# 328schema.net
KiCad netlist of a schematic drawn in EAGLE
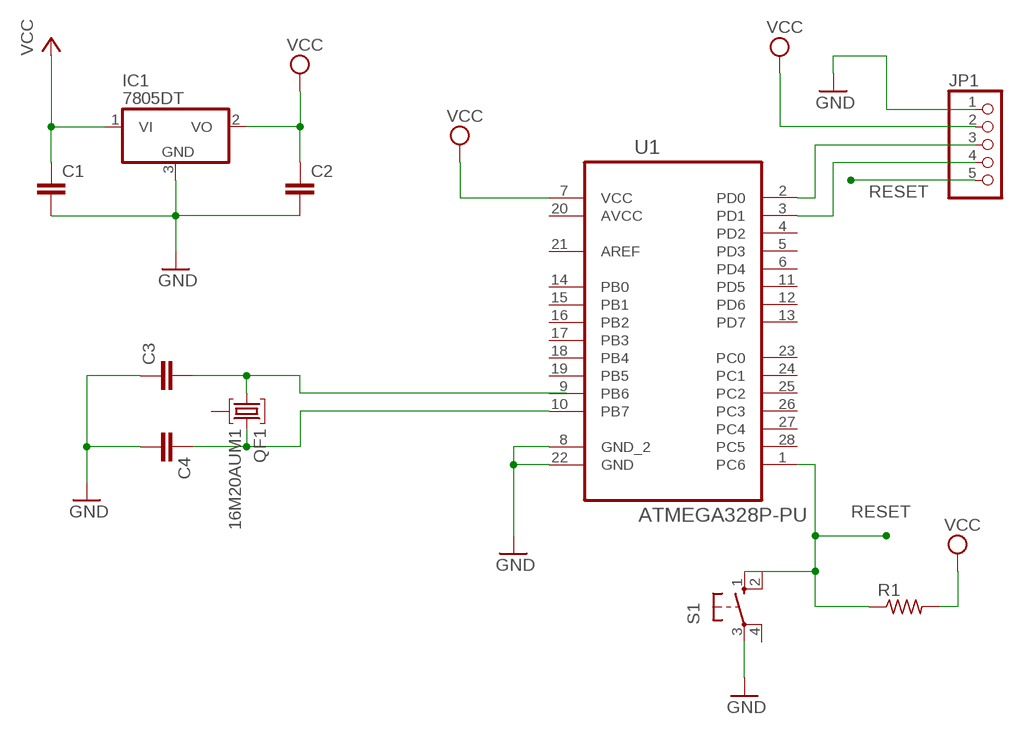
[diagram p0: schematic, sheet 1]

(export (version "E")
  (design (tool "Eeschema 10.0.6"))
  (components
    (comp (ref "C1")
      (value "C-EU025-025X050")
      (footprint "eagle-import:C025-025X050")
      (libsource (lib "eagle-import") (part "C-EU025-025X050"))
    )
    (comp (ref "C2")
      (value "C-EU025-025X050")
      (footprint "eagle-import:C025-025X050")
      (libsource (lib "eagle-import") (part "C-EU025-025X050"))
    )
    (comp (ref "C3")
      (value "C-EU025-025X050")
      (footprint "eagle-import:C025-025X050")
      (libsource (lib "eagle-import") (part "C-EU025-025X050"))
    )
    (comp (ref "C4")
      (value "C-EU025-025X050")
      (footprint "eagle-import:C025-025X050")
      (libsource (lib "eagle-import") (part "C-EU025-025X050"))
    )
    (comp (ref "IC1")
      (value "7805DT")
      (footprint "eagle-import:TO252")
      (libsource (lib "eagle-import") (part "78DT05"))
    )
    (comp (ref "JP1")
      (value "PINHD-1X5")
      (footprint "eagle-import:1X05")
      (libsource (lib "eagle-import") (part "PINHD-1X5"))
    )
    (comp (ref "QF1")
      (value "16M20AUM1")
      (footprint "eagle-import:UM1")
      (libsource (lib "eagle-import") (part "16M20AUM1"))
    )
    (comp (ref "R1")
      (value "R-US_0207/10")
      (footprint "eagle-import:0207_10")
      (libsource (lib "eagle-import") (part "R-US_0207/10"))
    )
    (comp (ref "S1")
      (value "10-XX")
      (footprint "eagle-import:B3F-10XX")
      (fields (field (name "MPN") "B3F-1000"))
      (libsource (lib "eagle-import") (part "10-XX"))
    )
    (comp (ref "U1")
      (value "ATMEGA328P-PU")
      (footprint "eagle-import:DIP254P762X457-28")
      (libsource (lib "eagle-import") (part "ATMEGA328P-PU"))
    )
  )
  (nets
    (net (code "1") (name "/AVCC") (class "Default")
      (node (ref "U1") (pin "20") (pinfunction "AVCC_20") (pintype "power_in"))
    )
    (net (code "2") (name "/RESET") (class "Default")
      (node (ref "JP1") (pin "5") (pinfunction "5_5") (pintype "passive"))
      (node (ref "R1") (pin "1") (pinfunction "1_1") (pintype "passive"))
      (node (ref "S1") (pin "1") (pinfunction "S_1") (pintype "passive"))
      (node (ref "U1") (pin "1") (pinfunction "PC6_1") (pintype "bidirectional"))
    )
    (net (code "3") (name "GND") (class "Default")
      (node (ref "C1") (pin "2") (pinfunction "2_2") (pintype "passive"))
      (node (ref "C2") (pin "2") (pinfunction "2_2") (pintype "passive"))
      (node (ref "C3") (pin "1") (pinfunction "1_1") (pintype "passive"))
      (node (ref "C4") (pin "2") (pinfunction "2_2") (pintype "passive"))
      (node (ref "IC1") (pin "3") (pinfunction "GND_3") (pintype "passive"))
      (node (ref "JP1") (pin "1") (pinfunction "1_1") (pintype "passive"))
      (node (ref "S1") (pin "3") (pinfunction "P_3") (pintype "passive"))
      (node (ref "U1") (pin "22") (pinfunction "GND_22") (pintype "passive"))
      (node (ref "U1") (pin "8") (pinfunction "GND_2_8") (pintype "passive"))
    )
    (net (code "4") (name "Net-(C3-Pad2)") (class "Default")
      (node (ref "C3") (pin "2") (pinfunction "2_2") (pintype "passive"))
      (node (ref "QF1") (pin "1") (pinfunction "1_1") (pintype "passive"))
    )
    (net (code "5") (name "Net-(U1-PB7)") (class "Default")
      (node (ref "C4") (pin "1") (pinfunction "1_1") (pintype "passive"))
      (node (ref "QF1") (pin "3") (pinfunction "3_3") (pintype "passive"))
      (node (ref "U1") (pin "10") (pinfunction "PB7_10") (pintype "bidirectional"))
    )
    (net (code "6") (name "Net-(U1-PD0)") (class "Default")
      (node (ref "JP1") (pin "3") (pinfunction "3_3") (pintype "passive"))
      (node (ref "U1") (pin "2") (pinfunction "PD0_2") (pintype "bidirectional"))
    )
    (net (code "7") (name "Net-(U1-PD1)") (class "Default")
      (node (ref "JP1") (pin "4") (pinfunction "4_4") (pintype "passive"))
      (node (ref "U1") (pin "3") (pinfunction "PD1_3") (pintype "bidirectional"))
    )
    (net (code "8") (name "VCC") (class "Default")
      (node (ref "C1") (pin "1") (pinfunction "1_1") (pintype "passive"))
      (node (ref "C2") (pin "1") (pinfunction "1_1") (pintype "passive"))
      (node (ref "IC1") (pin "1") (pinfunction "VI_1") (pintype "input"))
      (node (ref "IC1") (pin "2") (pinfunction "VO_2") (pintype "passive"))
      (node (ref "JP1") (pin "2") (pinfunction "2_2") (pintype "passive"))
      (node (ref "R1") (pin "2") (pinfunction "2_2") (pintype "passive"))
      (node (ref "U1") (pin "7") (pinfunction "VCC_7") (pintype "power_in"))
    )
    (net (code "9") (name "unconnected-(QF1-Pad2)") (class "Default")
      (node (ref "QF1") (pin "2") (pinfunction "2_2") (pintype "passive"))
    )
    (net (code "10") (name "unconnected-(S1-P1-Pad4)") (class "Default")
      (node (ref "S1") (pin "4") (pinfunction "P1_4") (pintype "passive"))
    )
    (net (code "11") (name "unconnected-(S1-S1-Pad2)") (class "Default")
      (node (ref "S1") (pin "2") (pinfunction "S1_2") (pintype "passive"))
    )
    (net (code "12") (name "unconnected-(U1-AREF-Pad21)") (class "Default")
      (node (ref "U1") (pin "21") (pinfunction "AREF_21") (pintype "input"))
    )
    (net (code "13") (name "unconnected-(U1-PB0-Pad14)") (class "Default")
      (node (ref "U1") (pin "14") (pinfunction "PB0_14") (pintype "bidirectional"))
    )
    (net (code "14") (name "unconnected-(U1-PB1-Pad15)") (class "Default")
      (node (ref "U1") (pin "15") (pinfunction "PB1_15") (pintype "bidirectional"))
    )
    (net (code "15") (name "unconnected-(U1-PB2-Pad16)") (class "Default")
      (node (ref "U1") (pin "16") (pinfunction "PB2_16") (pintype "bidirectional"))
    )
    (net (code "16") (name "unconnected-(U1-PB3-Pad17)") (class "Default")
      (node (ref "U1") (pin "17") (pinfunction "PB3_17") (pintype "bidirectional"))
    )
    (net (code "17") (name "unconnected-(U1-PB4-Pad18)") (class "Default")
      (node (ref "U1") (pin "18") (pinfunction "PB4_18") (pintype "bidirectional"))
    )
    (net (code "18") (name "unconnected-(U1-PB5-Pad19)") (class "Default")
      (node (ref "U1") (pin "19") (pinfunction "PB5_19") (pintype "bidirectional"))
    )
    (net (code "19") (name "unconnected-(U1-PB6-Pad9)") (class "Default")
      (node (ref "U1") (pin "9") (pinfunction "PB6_9") (pintype "bidirectional"))
    )
    (net (code "20") (name "unconnected-(U1-PC0-Pad23)") (class "Default")
      (node (ref "U1") (pin "23") (pinfunction "PC0_23") (pintype "bidirectional"))
    )
    (net (code "21") (name "unconnected-(U1-PC1-Pad24)") (class "Default")
      (node (ref "U1") (pin "24") (pinfunction "PC1_24") (pintype "bidirectional"))
    )
    (net (code "22") (name "unconnected-(U1-PC2-Pad25)") (class "Default")
      (node (ref "U1") (pin "25") (pinfunction "PC2_25") (pintype "bidirectional"))
    )
    (net (code "23") (name "unconnected-(U1-PC3-Pad26)") (class "Default")
      (node (ref "U1") (pin "26") (pinfunction "PC3_26") (pintype "bidirectional"))
    )
    (net (code "24") (name "unconnected-(U1-PC4-Pad27)") (class "Default")
      (node (ref "U1") (pin "27") (pinfunction "PC4_27") (pintype "bidirectional"))
    )
    (net (code "25") (name "unconnected-(U1-PC5-Pad28)") (class "Default")
      (node (ref "U1") (pin "28") (pinfunction "PC5_28") (pintype "bidirectional"))
    )
    (net (code "26") (name "unconnected-(U1-PD2-Pad4)") (class "Default")
      (node (ref "U1") (pin "4") (pinfunction "PD2_4") (pintype "bidirectional"))
    )
    (net (code "27") (name "unconnected-(U1-PD3-Pad5)") (class "Default")
      (node (ref "U1") (pin "5") (pinfunction "PD3_5") (pintype "bidirectional"))
    )
    (net (code "28") (name "unconnected-(U1-PD4-Pad6)") (class "Default")
      (node (ref "U1") (pin "6") (pinfunction "PD4_6") (pintype "bidirectional"))
    )
    (net (code "29") (name "unconnected-(U1-PD5-Pad11)") (class "Default")
      (node (ref "U1") (pin "11") (pinfunction "PD5_11") (pintype "bidirectional"))
    )
    (net (code "30") (name "unconnected-(U1-PD6-Pad12)") (class "Default")
      (node (ref "U1") (pin "12") (pinfunction "PD6_12") (pintype "bidirectional"))
    )
    (net (code "31") (name "unconnected-(U1-PD7-Pad13)") (class "Default")
      (node (ref "U1") (pin "13") (pinfunction "PD7_13") (pintype "bidirectional"))
    )
  )
)
